# BLDC.net
KiCad netlist of a schematic drawn in EAGLE
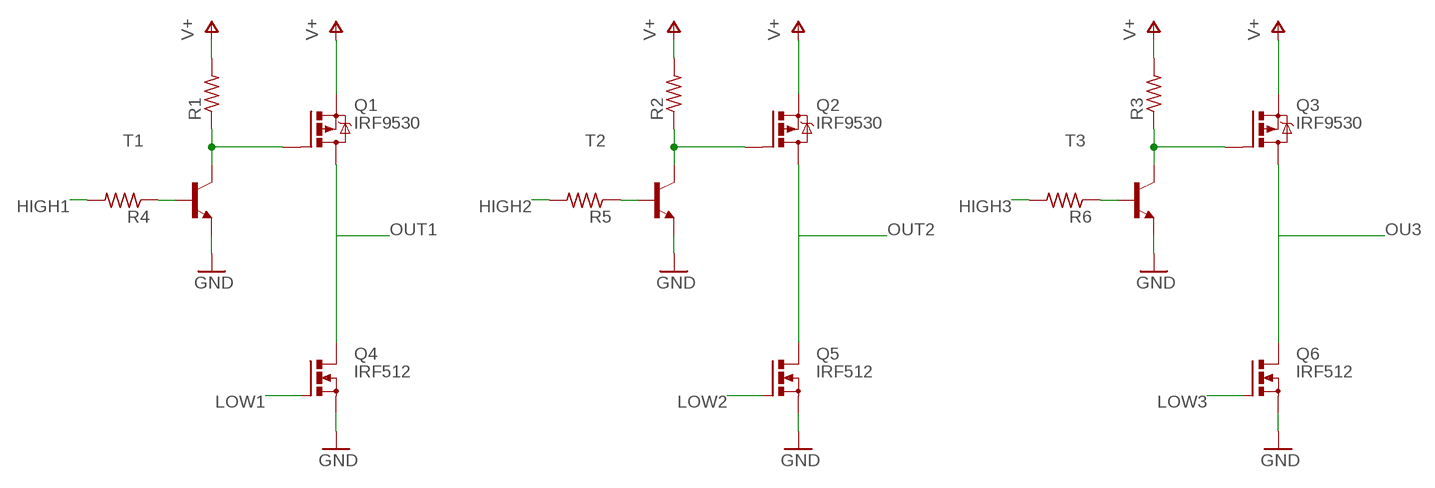
[diagram p0: schematic, sheet 1]

(export (version "E")
  (design (tool "Eeschema 10.0.6"))
  (components
    (comp (ref "Q1")
      (value "IRF9530")
      (footprint "eagle-import:TO220BV")
      (libsource (lib "eagle-import") (part "IRF9530"))
    )
    (comp (ref "Q2")
      (value "IRF9530")
      (footprint "eagle-import:TO220BV")
      (libsource (lib "eagle-import") (part "IRF9530"))
    )
    (comp (ref "Q3")
      (value "IRF9530")
      (footprint "eagle-import:TO220BV")
      (libsource (lib "eagle-import") (part "IRF9530"))
    )
    (comp (ref "Q4")
      (value "IRF512")
      (footprint "eagle-import:TO220BV")
      (libsource (lib "eagle-import") (part "IRF512"))
    )
    (comp (ref "Q5")
      (value "IRF512")
      (footprint "eagle-import:TO220BV")
      (libsource (lib "eagle-import") (part "IRF512"))
    )
    (comp (ref "Q6")
      (value "IRF512")
      (footprint "eagle-import:TO220BV")
      (libsource (lib "eagle-import") (part "IRF512"))
    )
    (comp (ref "R1")
      (value "R-US_0204/7")
      (footprint "eagle-import:0204_7")
      (libsource (lib "eagle-import") (part "R-US_0204/7"))
    )
    (comp (ref "R2")
      (value "R-US_0204/7")
      (footprint "eagle-import:0204_7")
      (libsource (lib "eagle-import") (part "R-US_0204/7"))
    )
    (comp (ref "R3")
      (value "R-US_0204/7")
      (footprint "eagle-import:0204_7")
      (libsource (lib "eagle-import") (part "R-US_0204/7"))
    )
    (comp (ref "R4")
      (value "R-US_0204/7")
      (footprint "eagle-import:0204_7")
      (libsource (lib "eagle-import") (part "R-US_0204/7"))
    )
    (comp (ref "R5")
      (value "R-US_0204/7")
      (footprint "eagle-import:0204_7")
      (libsource (lib "eagle-import") (part "R-US_0204/7"))
    )
    (comp (ref "R6")
      (value "R-US_0204/7")
      (footprint "eagle-import:0204_7")
      (libsource (lib "eagle-import") (part "R-US_0204/7"))
    )
    (comp (ref "T1")
      (value "-NPN-TO92-BEC")
      (footprint "eagle-import:TO92-BEC")
      (libsource (lib "eagle-import") (part "-NPN-TO92-BEC"))
    )
    (comp (ref "T2")
      (value "-NPN-TO92-BEC")
      (footprint "eagle-import:TO92-BEC")
      (libsource (lib "eagle-import") (part "-NPN-TO92-BEC"))
    )
    (comp (ref "T3")
      (value "-NPN-TO92-BEC")
      (footprint "eagle-import:TO92-BEC")
      (libsource (lib "eagle-import") (part "-NPN-TO92-BEC"))
    )
  )
  (nets
    (net (code "1") (name "/HIGH1") (class "Default")
      (node (ref "R4") (pin "2") (pinfunction "2_2") (pintype "passive"))
    )
    (net (code "2") (name "/HIGH2") (class "Default")
      (node (ref "R5") (pin "2") (pinfunction "2_2") (pintype "passive"))
    )
    (net (code "3") (name "/HIGH3") (class "Default")
      (node (ref "R6") (pin "2") (pinfunction "2_2") (pintype "passive"))
    )
    (net (code "4") (name "/LOW1") (class "Default")
      (node (ref "Q4") (pin "G") (pinfunction "G_G") (pintype "passive"))
    )
    (net (code "5") (name "/LOW2") (class "Default")
      (node (ref "Q5") (pin "G") (pinfunction "G_G") (pintype "passive"))
    )
    (net (code "6") (name "/LOW3") (class "Default")
      (node (ref "Q6") (pin "G") (pinfunction "G_G") (pintype "passive"))
    )
    (net (code "7") (name "/OU3") (class "Default")
      (node (ref "Q3") (pin "D") (pinfunction "D_D") (pintype "passive"))
      (node (ref "Q6") (pin "D") (pinfunction "D_D") (pintype "passive"))
    )
    (net (code "8") (name "/OUT1") (class "Default")
      (node (ref "Q1") (pin "D") (pinfunction "D_D") (pintype "passive"))
      (node (ref "Q4") (pin "D") (pinfunction "D_D") (pintype "passive"))
    )
    (net (code "9") (name "/OUT2") (class "Default")
      (node (ref "Q2") (pin "D") (pinfunction "D_D") (pintype "passive"))
      (node (ref "Q5") (pin "D") (pinfunction "D_D") (pintype "passive"))
    )
    (net (code "10") (name "GND") (class "Default")
      (node (ref "Q4") (pin "S") (pinfunction "S_S") (pintype "passive"))
      (node (ref "Q5") (pin "S") (pinfunction "S_S") (pintype "passive"))
      (node (ref "Q6") (pin "S") (pinfunction "S_S") (pintype "passive"))
      (node (ref "T1") (pin "E") (pinfunction "E_E") (pintype "passive"))
      (node (ref "T2") (pin "E") (pinfunction "E_E") (pintype "passive"))
      (node (ref "T3") (pin "E") (pinfunction "E_E") (pintype "passive"))
    )
    (net (code "11") (name "Net-(Q1-PadG)") (class "Default")
      (node (ref "Q1") (pin "G") (pinfunction "G_G") (pintype "passive"))
      (node (ref "R1") (pin "1") (pinfunction "1_1") (pintype "passive"))
      (node (ref "T1") (pin "C") (pinfunction "C_C") (pintype "passive"))
    )
    (net (code "12") (name "Net-(Q2-PadG)") (class "Default")
      (node (ref "Q2") (pin "G") (pinfunction "G_G") (pintype "passive"))
      (node (ref "R2") (pin "1") (pinfunction "1_1") (pintype "passive"))
      (node (ref "T2") (pin "C") (pinfunction "C_C") (pintype "passive"))
    )
    (net (code "13") (name "Net-(Q3-PadG)") (class "Default")
      (node (ref "Q3") (pin "G") (pinfunction "G_G") (pintype "passive"))
      (node (ref "R3") (pin "1") (pinfunction "1_1") (pintype "passive"))
      (node (ref "T3") (pin "C") (pinfunction "C_C") (pintype "passive"))
    )
    (net (code "14") (name "Net-(R4-Pad1)") (class "Default")
      (node (ref "R4") (pin "1") (pinfunction "1_1") (pintype "passive"))
      (node (ref "T1") (pin "B") (pinfunction "B_B") (pintype "passive"))
    )
    (net (code "15") (name "Net-(R5-Pad1)") (class "Default")
      (node (ref "R5") (pin "1") (pinfunction "1_1") (pintype "passive"))
      (node (ref "T2") (pin "B") (pinfunction "B_B") (pintype "passive"))
    )
    (net (code "16") (name "Net-(R6-Pad1)") (class "Default")
      (node (ref "R6") (pin "1") (pinfunction "1_1") (pintype "passive"))
      (node (ref "T3") (pin "B") (pinfunction "B_B") (pintype "passive"))
    )
    (net (code "17") (name "V+") (class "Default")
      (node (ref "Q1") (pin "S") (pinfunction "S_S") (pintype "passive"))
      (node (ref "Q2") (pin "S") (pinfunction "S_S") (pintype "passive"))
      (node (ref "Q3") (pin "S") (pinfunction "S_S") (pintype "passive"))
      (node (ref "R1") (pin "2") (pinfunction "2_2") (pintype "passive"))
      (node (ref "R2") (pin "2") (pinfunction "2_2") (pintype "passive"))
      (node (ref "R3") (pin "2") (pinfunction "2_2") (pintype "passive"))
    )
  )
)
